# LCD.net
KiCad netlist of a schematic drawn in Altium Designer
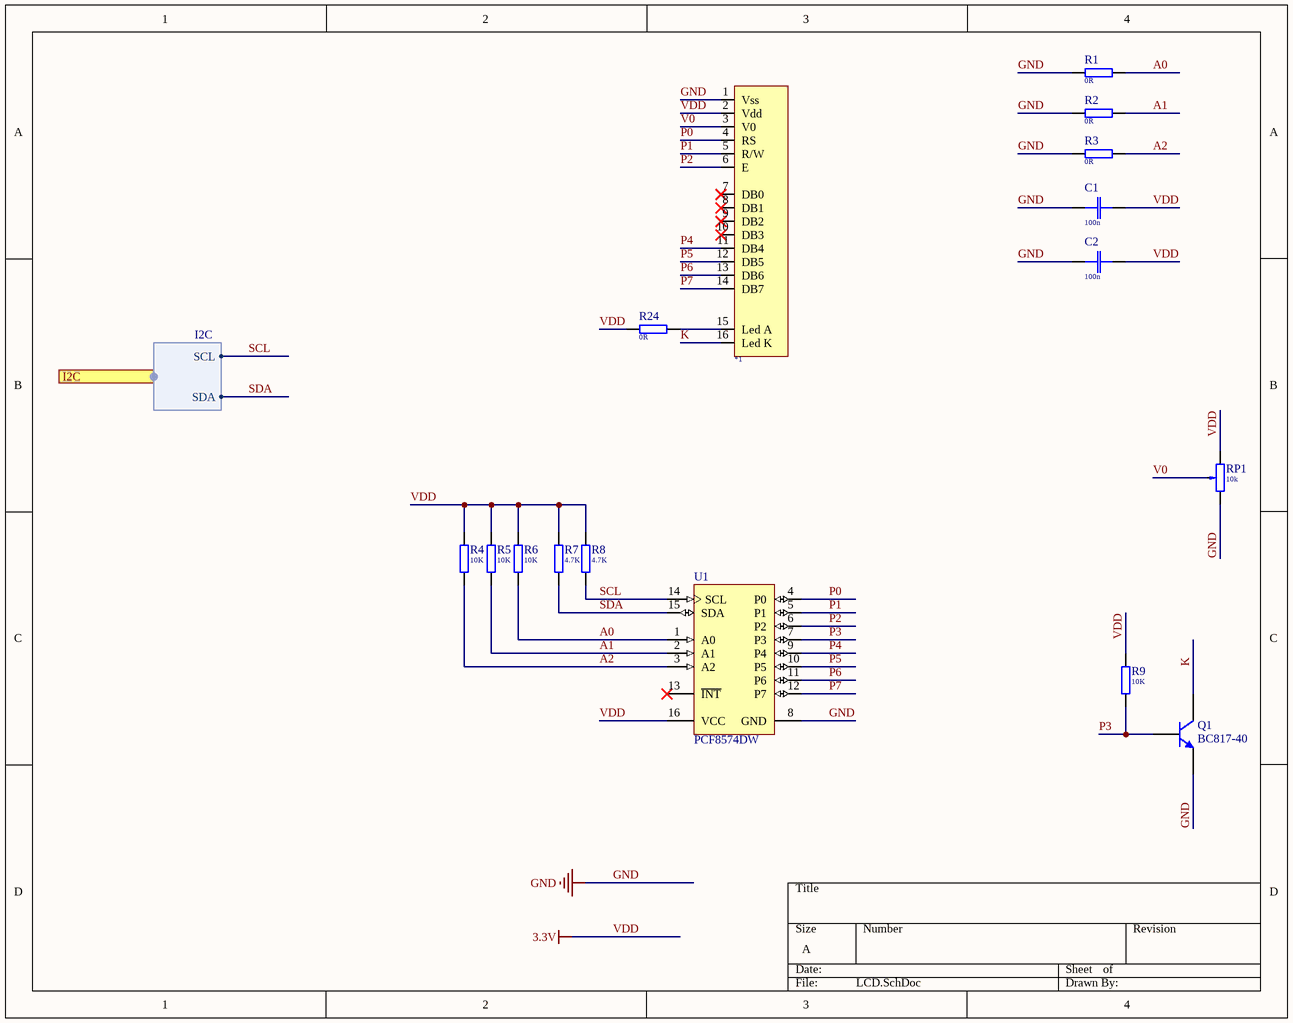
[diagram p0: LCD.SchDoc]

(export (version "E")
  (design (tool "Eeschema 10.0.6"))
  (components
    (comp (ref "*1")
      (value "AC162B 2x16")
      (footprint "AC-162B 2x16")
      (libsource (lib "Ind LED-LCD") (part "AC162B 2x16"))
    )
    (comp (ref "C1")
      (value "100n")
      (footprint "C0805(2013)")
      (description "SMD-0805 50V Y5V +80/-20%")
      (libsource (lib "SMD-RCL") (part "C-0805   50V 100n"))
    )
    (comp (ref "C2")
      (value "100n")
      (footprint "C0805(2013)")
      (description "SMD-0805 50V Y5V +80/-20%")
      (libsource (lib "SMD-RCL") (part "C-0805   50V 100n"))
    )
    (comp (ref "Q1")
      (value "BC817-40")
      (footprint "SOT23_N")
      (description "NPN General-purpose Transistor")
      (fields (field (name "PUBLISHER") "Altium Limited"))
      (libsource (lib "Philips Discrete BJT - Low Power") (part "BC817-40"))
    )
    (comp (ref "R1")
      (value "0R")
      (footprint "R0805")
      (description "SMD 0805 0.1W 5% 150V")
      (libsource (lib "SMD-RCL") (part "R-0805"))
    )
    (comp (ref "R2")
      (value "0R")
      (footprint "R0805")
      (description "SMD 0805 0.1W 5% 150V")
      (libsource (lib "SMD-RCL") (part "R-0805"))
    )
    (comp (ref "R3")
      (value "0R")
      (footprint "R0805")
      (description "SMD 0805 0.1W 5% 150V")
      (libsource (lib "SMD-RCL") (part "R-0805"))
    )
    (comp (ref "R4")
      (value "10K")
      (footprint "R0805")
      (description "SMD 0805 0.1W 5% 150V")
      (libsource (lib "SMD-RCL") (part "R-0805"))
    )
    (comp (ref "R5")
      (value "10K")
      (footprint "R0805")
      (description "SMD 0805 0.1W 5% 150V")
      (libsource (lib "SMD-RCL") (part "R-0805"))
    )
    (comp (ref "R6")
      (value "10K")
      (footprint "R0805")
      (description "SMD 0805 0.1W 5% 150V")
      (libsource (lib "SMD-RCL") (part "R-0805"))
    )
    (comp (ref "R7")
      (value "4.7K")
      (footprint "R0805")
      (description "SMD 0805 0.1W 5% 150V")
      (libsource (lib "SMD-RCL") (part "R-0805"))
    )
    (comp (ref "R8")
      (value "4.7K")
      (footprint "R0805")
      (description "SMD 0805 0.1W 5% 150V")
      (libsource (lib "SMD-RCL") (part "R-0805"))
    )
    (comp (ref "R9")
      (value "10K")
      (footprint "R0805")
      (description "SMD 0805 0.1W 5% 150V")
      (libsource (lib "SMD-RCL") (part "R-0805"))
    )
    (comp (ref "R24")
      (value "0R")
      (footprint "R0805")
      (description "SMD 0805 0.1W 5% 150V")
      (libsource (lib "SMD-RCL") (part "R-0805"))
    )
    (comp (ref "RP1")
      (value "10k")
      (footprint "R-Tr 3362P")
      (description "Bourns 3362F 0.5W")
      (libsource (lib "Rez-Axial Pot") (part "R-Tr 3362F"))
    )
    (comp (ref "U1")
      (value "PCF8574DW")
      (footprint "DW16_N")
      (fields (field (name "MANUFACTURER") "Texas Instruments"))
      (libsource (lib "Texas Instruments Interface I2C") (part "PCF8574DW"))
    )
  )
  (nets
    (net (code "2") (name "/A0") (class "Default")
      (node (ref "R1") (pin "1") (pinfunction "1_1") (pintype "passive"))
      (node (ref "R6") (pin "1") (pinfunction "1_1") (pintype "passive"))
      (node (ref "U1") (pin "1") (pinfunction "A0_1") (pintype "input"))
    )
    (net (code "3") (name "/A1") (class "Default")
      (node (ref "R2") (pin "1") (pinfunction "1_1") (pintype "passive"))
      (node (ref "R5") (pin "1") (pinfunction "1_1") (pintype "passive"))
      (node (ref "U1") (pin "2") (pinfunction "A1_2") (pintype "input"))
    )
    (net (code "4") (name "/A2") (class "Default")
      (node (ref "R3") (pin "1") (pinfunction "1_1") (pintype "passive"))
      (node (ref "R4") (pin "1") (pinfunction "1_1") (pintype "passive"))
      (node (ref "U1") (pin "3") (pinfunction "A2_3") (pintype "input"))
    )
    (net (code "5") (name "/K") (class "Default")
      (node (ref "*1") (pin "16") (pinfunction "Led_K_16") (pintype "passive"))
      (node (ref "Q1") (pin "3") (pinfunction "C_3") (pintype "passive"))
    )
    (net (code "6") (name "/P0") (class "Default")
      (node (ref "*1") (pin "4") (pinfunction "RS_4") (pintype "passive"))
      (node (ref "U1") (pin "4") (pinfunction "P0_4") (pintype "bidirectional"))
    )
    (net (code "7") (name "/P1") (class "Default")
      (node (ref "*1") (pin "5") (pinfunction "R/W_5") (pintype "passive"))
      (node (ref "U1") (pin "5") (pinfunction "P1_5") (pintype "bidirectional"))
    )
    (net (code "8") (name "/P2") (class "Default")
      (node (ref "*1") (pin "6") (pinfunction "E_6") (pintype "passive"))
      (node (ref "U1") (pin "6") (pinfunction "P2_6") (pintype "bidirectional"))
    )
    (net (code "9") (name "/P3") (class "Default")
      (node (ref "Q1") (pin "1") (pinfunction "B_1") (pintype "passive"))
      (node (ref "R9") (pin "1") (pinfunction "1_1") (pintype "passive"))
      (node (ref "U1") (pin "7") (pinfunction "P3_7") (pintype "bidirectional"))
    )
    (net (code "10") (name "/P4") (class "Default")
      (node (ref "*1") (pin "11") (pinfunction "DB4_11") (pintype "passive"))
      (node (ref "U1") (pin "9") (pinfunction "P4_9") (pintype "bidirectional"))
    )
    (net (code "11") (name "/P5") (class "Default")
      (node (ref "*1") (pin "12") (pinfunction "DB5_12") (pintype "passive"))
      (node (ref "U1") (pin "10") (pinfunction "P5_10") (pintype "bidirectional"))
    )
    (net (code "12") (name "/P6") (class "Default")
      (node (ref "*1") (pin "13") (pinfunction "DB6_13") (pintype "passive"))
      (node (ref "U1") (pin "11") (pinfunction "P6_11") (pintype "bidirectional"))
    )
    (net (code "13") (name "/P7") (class "Default")
      (node (ref "*1") (pin "14") (pinfunction "DB7_14") (pintype "passive"))
      (node (ref "U1") (pin "12") (pinfunction "P7_12") (pintype "bidirectional"))
    )
    (net (code "14") (name "/SCL") (class "Default")
      (node (ref "R8") (pin "1") (pinfunction "1_1") (pintype "passive"))
      (node (ref "U1") (pin "14") (pinfunction "SCL_14") (pintype "input"))
    )
    (net (code "15") (name "/SDA") (class "Default")
      (node (ref "R7") (pin "1") (pinfunction "1_1") (pintype "passive"))
      (node (ref "U1") (pin "15") (pinfunction "SDA_15") (pintype "bidirectional"))
    )
    (net (code "16") (name "/V0") (class "Default")
      (node (ref "*1") (pin "3") (pinfunction "V0_3") (pintype "passive"))
      (node (ref "RP1") (pin "2") (pinfunction "2_2") (pintype "passive"))
    )
    (net (code "18") (name "3.3V") (class "Default")
      (node (ref "*1") (pin "2") (pinfunction "Vdd_2") (pintype "passive"))
      (node (ref "C1") (pin "2") (pinfunction "2_2") (pintype "passive"))
      (node (ref "C2") (pin "2") (pinfunction "2_2") (pintype "passive"))
      (node (ref "R24") (pin "2") (pinfunction "2_2") (pintype "passive"))
      (node (ref "R4") (pin "2") (pinfunction "2_2") (pintype "passive"))
      (node (ref "R5") (pin "2") (pinfunction "2_2") (pintype "passive"))
      (node (ref "R6") (pin "2") (pinfunction "2_2") (pintype "passive"))
      (node (ref "R7") (pin "2") (pinfunction "2_2") (pintype "passive"))
      (node (ref "R8") (pin "2") (pinfunction "2_2") (pintype "passive"))
      (node (ref "R9") (pin "2") (pinfunction "2_2") (pintype "passive"))
      (node (ref "RP1") (pin "3") (pinfunction "3_3") (pintype "passive"))
      (node (ref "U1") (pin "16") (pinfunction "VCC_16") (pintype "power_in"))
    )
    (net (code "19") (name "GND") (class "Default")
      (node (ref "*1") (pin "1") (pinfunction "Vss_1") (pintype "passive"))
      (node (ref "C1") (pin "1") (pinfunction "1_1") (pintype "passive"))
      (node (ref "C2") (pin "1") (pinfunction "1_1") (pintype "passive"))
      (node (ref "Q1") (pin "2") (pinfunction "E_2") (pintype "passive"))
      (node (ref "R1") (pin "2") (pinfunction "2_2") (pintype "passive"))
      (node (ref "R2") (pin "2") (pinfunction "2_2") (pintype "passive"))
      (node (ref "R3") (pin "2") (pinfunction "2_2") (pintype "passive"))
      (node (ref "RP1") (pin "1") (pinfunction "1_1") (pintype "passive"))
      (node (ref "U1") (pin "8") (pinfunction "GND_8") (pintype "power_in"))
    )
    (net (code "20") (name "Net-(*1-Led_A)") (class "Default")
      (node (ref "*1") (pin "15") (pinfunction "Led_A_15") (pintype "passive"))
      (node (ref "R24") (pin "1") (pinfunction "1_1") (pintype "passive"))
    )
    (net (code "21") (name "unconnected-(*1-DB0-Pad7)") (class "Default")
      (node (ref "*1") (pin "7") (pinfunction "DB0_7") (pintype "passive+no_connect"))
    )
    (net (code "22") (name "unconnected-(*1-DB1-Pad8)") (class "Default")
      (node (ref "*1") (pin "8") (pinfunction "DB1_8") (pintype "passive+no_connect"))
    )
    (net (code "23") (name "unconnected-(*1-DB2-Pad9)") (class "Default")
      (node (ref "*1") (pin "9") (pinfunction "DB2_9") (pintype "passive+no_connect"))
    )
    (net (code "24") (name "unconnected-(*1-DB3-Pad10)") (class "Default")
      (node (ref "*1") (pin "10") (pinfunction "DB3_10") (pintype "passive+no_connect"))
    )
    (net (code "25") (name "unconnected-(U1-~{INT}-Pad13)") (class "Default")
      (node (ref "U1") (pin "13") (pinfunction "~{INT}_13") (pintype "open_collector+no_connect"))
    )
  )
)
